# power-supply.net
KiCad netlist of a schematic drawn in EAGLE
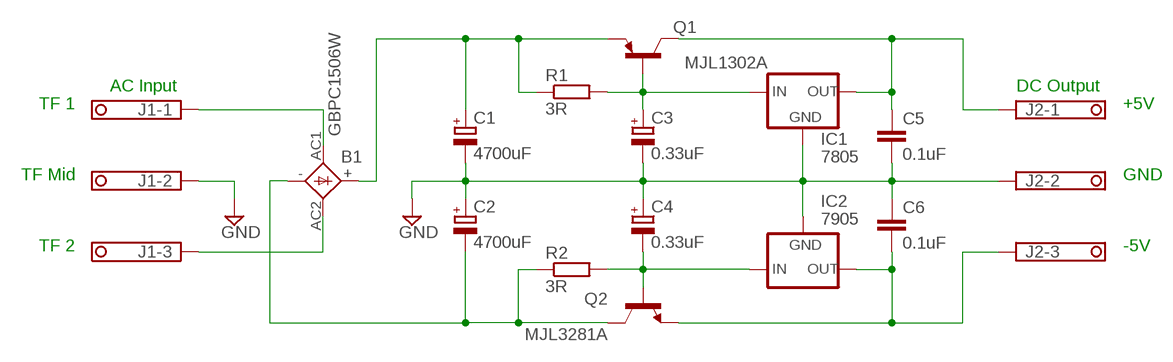
[diagram p0: schematic, sheet 1]

(export (version "E")
  (design (tool "Eeschema 10.0.6"))
  (components
    (comp (ref "B1")
      (value "GBPC1506W")
      (footprint "eagle-import:GBPC6")
      (libsource (lib "eagle-import") (part "GBPC6"))
    )
    (comp (ref "C1")
      (value "4700uF")
      (footprint "eagle-import:E7,5-16")
      (libsource (lib "eagle-import") (part "CPOL-EUE7.5-16"))
    )
    (comp (ref "C2")
      (value "4700uF")
      (footprint "eagle-import:E7,5-16")
      (libsource (lib "eagle-import") (part "CPOL-EUE7.5-16"))
    )
    (comp (ref "C3")
      (value "0.33uF")
      (footprint "eagle-import:E2,5-5")
      (libsource (lib "eagle-import") (part "CPOL-EUE2.5-5"))
    )
    (comp (ref "C4")
      (value "0.33uF")
      (footprint "eagle-import:E2,5-5")
      (libsource (lib "eagle-import") (part "CPOL-EUE2.5-5"))
    )
    (comp (ref "C5")
      (value "0.1uF")
      (footprint "eagle-import:C102-054X133")
      (libsource (lib "eagle-import") (part "C-EU102-054X133"))
    )
    (comp (ref "C6")
      (value "0.1uF")
      (footprint "eagle-import:C102-054X133")
      (libsource (lib "eagle-import") (part "C-EU102-054X133"))
    )
    (comp (ref "IC1")
      (value "7805")
      (footprint "eagle-import:78XXS")
      (libsource (lib "eagle-import") (part "78XXS"))
    )
    (comp (ref "IC2")
      (value "7905")
      (footprint "eagle-import:79XXS")
      (libsource (lib "eagle-import") (part "79XXS"))
    )
    (comp (ref "J1")
      (value "1751251")
      (footprint "eagle-import:1751251")
      (libsource (lib "eagle-import") (part "1751251"))
    )
    (comp (ref "J2")
      (value "1751251")
      (footprint "eagle-import:1751251")
      (libsource (lib "eagle-import") (part "1751251"))
    )
    (comp (ref "Q1")
      (value "MJL1302A")
      (footprint "eagle-import:TO-264")
      (libsource (lib "eagle-import") (part "MJL1302A"))
    )
    (comp (ref "Q2")
      (value "MJL3281A")
      (footprint "eagle-import:TO-264")
      (libsource (lib "eagle-import") (part "MJL3281A"))
    )
    (comp (ref "R1")
      (value "3R")
      (footprint "eagle-import:0411_15")
      (libsource (lib "eagle-import") (part "R-EU_0411/15"))
    )
    (comp (ref "R2")
      (value "3R")
      (footprint "eagle-import:0411_15")
      (libsource (lib "eagle-import") (part "R-EU_0411/15"))
    )
  )
  (nets
    (net (code "1") (name "GND") (class "Default")
      (node (ref "C1") (pin "-") (pinfunction "-_-") (pintype "passive"))
      (node (ref "C2") (pin "+") (pinfunction "+_+") (pintype "passive"))
      (node (ref "C3") (pin "-") (pinfunction "-_-") (pintype "passive"))
      (node (ref "C4") (pin "+") (pinfunction "+_+") (pintype "passive"))
      (node (ref "C5") (pin "2") (pinfunction "2_2") (pintype "passive"))
      (node (ref "C6") (pin "1") (pinfunction "1_1") (pintype "passive"))
      (node (ref "IC1") (pin "GND") (pinfunction "GND_GND") (pintype "input"))
      (node (ref "IC2") (pin "GND") (pinfunction "GND_GND") (pintype "input"))
      (node (ref "J1") (pin "2") (pinfunction "K_2") (pintype "passive"))
      (node (ref "J2") (pin "2") (pinfunction "K_2") (pintype "passive"))
    )
    (net (code "2") (name "Net-(B1-Pad+)") (class "Default")
      (node (ref "B1") (pin "+") (pinfunction "+_+") (pintype "passive"))
      (node (ref "C1") (pin "+") (pinfunction "+_+") (pintype "passive"))
      (node (ref "Q1") (pin "EMITTER") (pinfunction "EMITTER_EMITTER") (pintype "passive"))
      (node (ref "R1") (pin "1") (pinfunction "1_1") (pintype "passive"))
    )
    (net (code "3") (name "Net-(B1-Pad-)") (class "Default")
      (node (ref "B1") (pin "-") (pinfunction "-_-") (pintype "passive"))
      (node (ref "C2") (pin "-") (pinfunction "-_-") (pintype "passive"))
      (node (ref "Q2") (pin "COLLECTOR") (pinfunction "COLLECTOR_COLLECTOR") (pintype "passive"))
      (node (ref "R2") (pin "1") (pinfunction "1_1") (pintype "passive"))
    )
    (net (code "4") (name "Net-(C3-Pad+)") (class "Default")
      (node (ref "C3") (pin "+") (pinfunction "+_+") (pintype "passive"))
      (node (ref "IC1") (pin "IN") (pinfunction "IN_IN") (pintype "input"))
      (node (ref "Q1") (pin "BASE") (pinfunction "BASE_BASE") (pintype "passive"))
      (node (ref "R1") (pin "2") (pinfunction "2_2") (pintype "passive"))
    )
    (net (code "5") (name "Net-(C4-Pad-)") (class "Default")
      (node (ref "C4") (pin "-") (pinfunction "-_-") (pintype "passive"))
      (node (ref "IC2") (pin "IN") (pinfunction "IN_IN") (pintype "input"))
      (node (ref "Q2") (pin "BASE") (pinfunction "BASE_BASE") (pintype "passive"))
      (node (ref "R2") (pin "2") (pinfunction "2_2") (pintype "passive"))
    )
    (net (code "6") (name "Net-(J1A-K)") (class "Default")
      (node (ref "B1") (pin "AC1") (pinfunction "AC1_AC1") (pintype "passive"))
      (node (ref "J1") (pin "1") (pinfunction "K_1") (pintype "passive"))
    )
    (net (code "7") (name "Net-(J1C-K)") (class "Default")
      (node (ref "B1") (pin "AC2") (pinfunction "AC2_AC2") (pintype "passive"))
      (node (ref "J1") (pin "3") (pinfunction "K_3") (pintype "passive"))
    )
    (net (code "8") (name "Net-(J2A-K)") (class "Default")
      (node (ref "C5") (pin "1") (pinfunction "1_1") (pintype "passive"))
      (node (ref "IC1") (pin "OUT") (pinfunction "OUT_OUT") (pintype "passive"))
      (node (ref "J2") (pin "1") (pinfunction "K_1") (pintype "passive"))
      (node (ref "Q1") (pin "COLLECTOR") (pinfunction "COLLECTOR_COLLECTOR") (pintype "passive"))
    )
    (net (code "9") (name "Net-(J2C-K)") (class "Default")
      (node (ref "C6") (pin "2") (pinfunction "2_2") (pintype "passive"))
      (node (ref "IC2") (pin "OUT") (pinfunction "OUT_OUT") (pintype "passive"))
      (node (ref "J2") (pin "3") (pinfunction "K_3") (pintype "passive"))
      (node (ref "Q2") (pin "EMITTER") (pinfunction "EMITTER_EMITTER") (pintype "passive"))
    )
  )
)
